# schematic_tsc.net
KiCad netlist of a schematic drawn in EAGLE
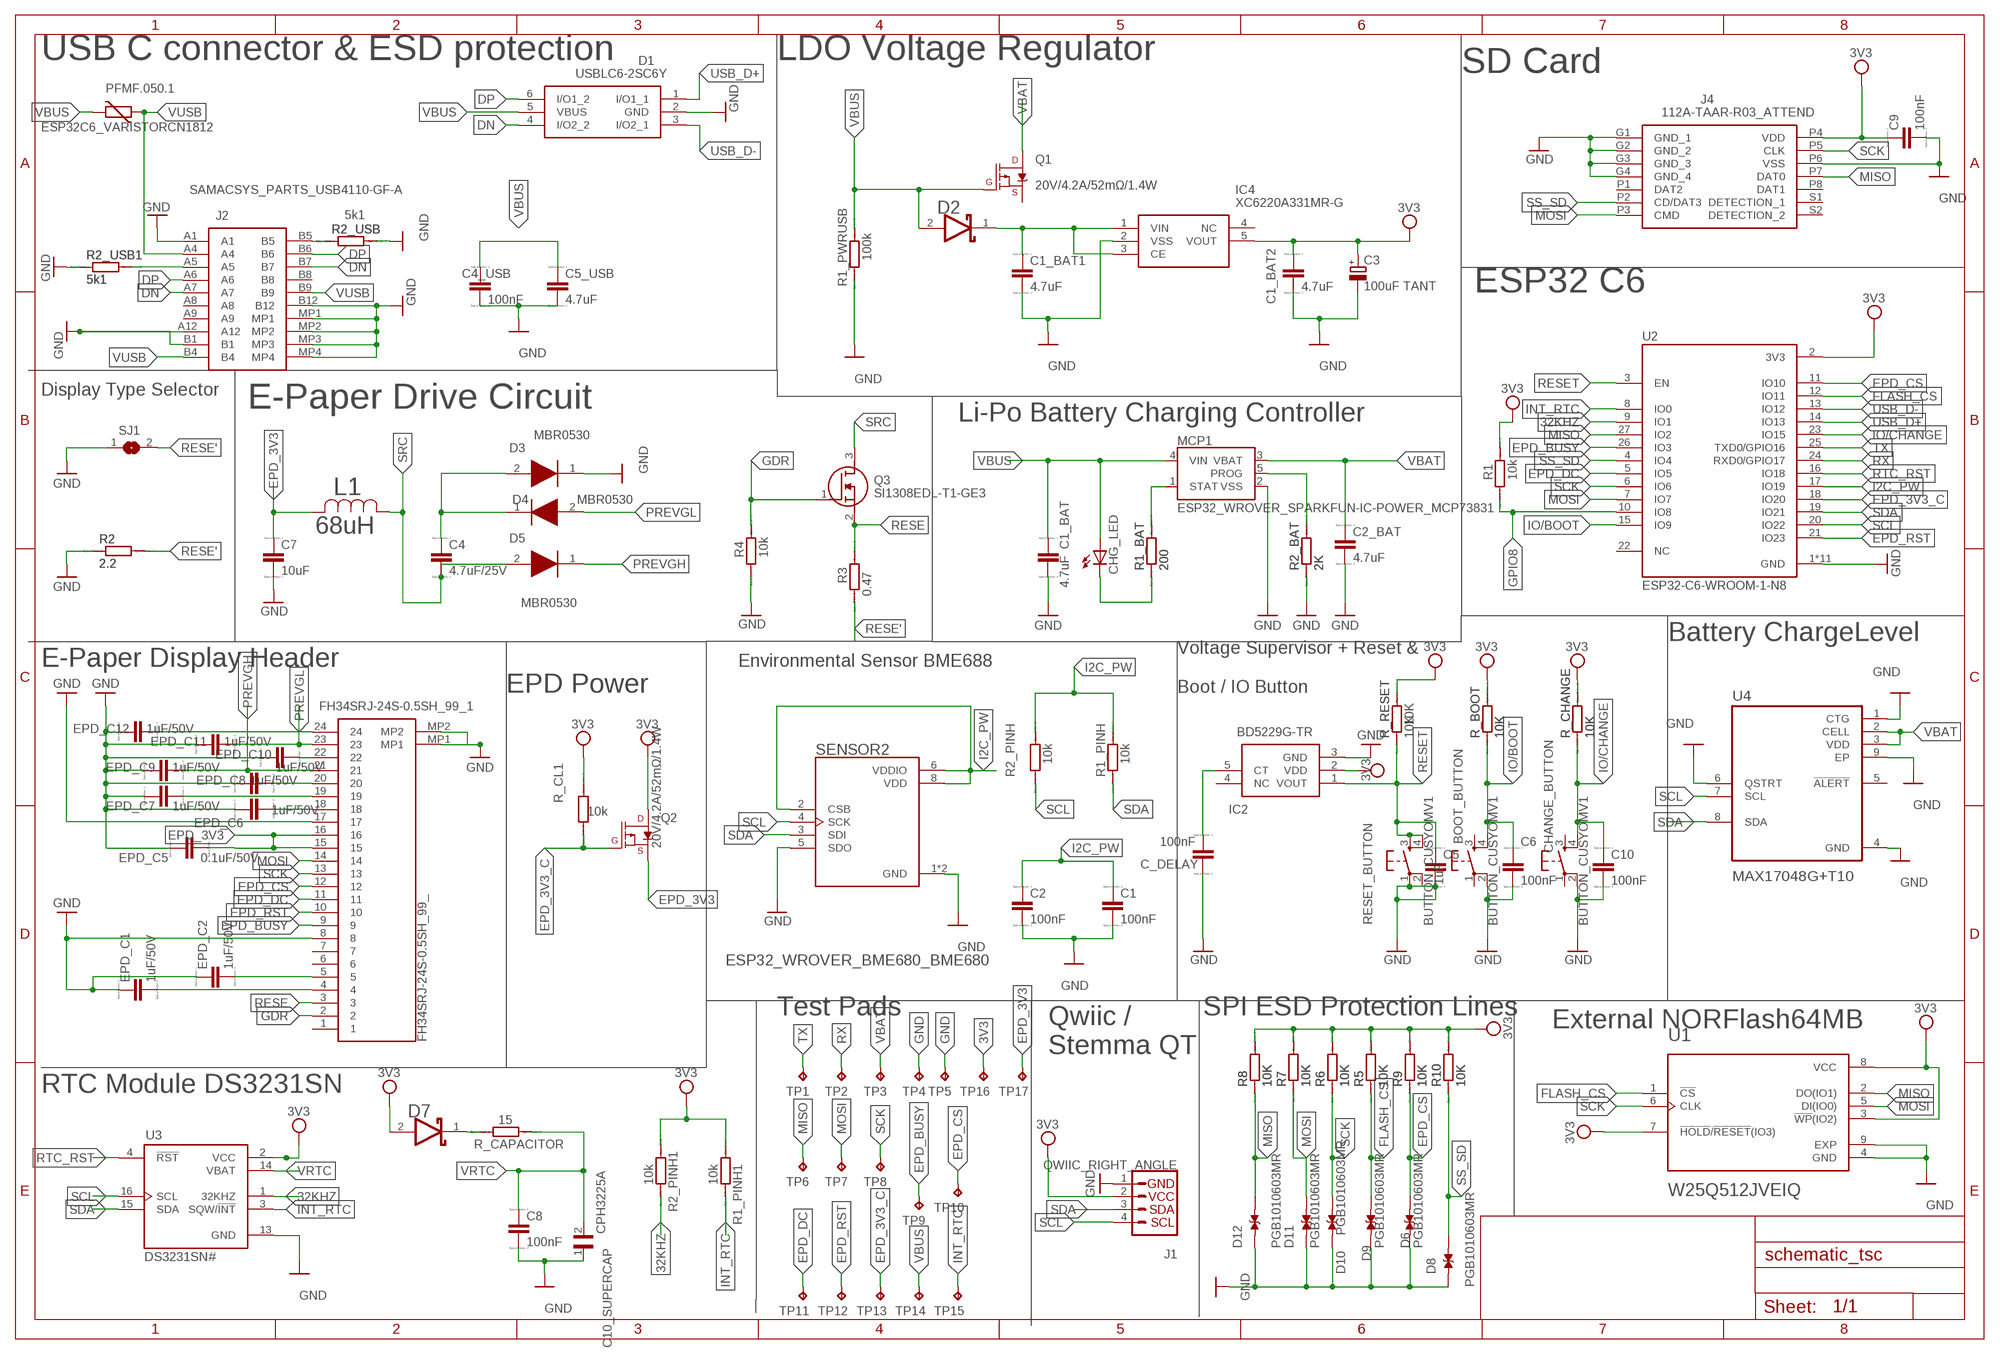
[diagram p0: schematic, sheet 1]

(export (version "E")
  (design (tool "Eeschema 10.0.6"))
  (components
    (comp (ref "BOOT_BUTTON")
      (value "BUTTON_CUSYOMV1")
      (footprint "eagle-import:MYBUTTON")
      (libsource (lib "eagle-import") (part "BUTTON_CUSYOMV1"))
    )
    (comp (ref "C1")
      (value "100nF")
      (footprint "eagle-import:EAGLE-LTSPICE_C0402")
      (libsource (lib "eagle-import") (part "EAGLE-LTSPICE_CC0402"))
    )
    (comp (ref "C1_BAT")
      (value "4.7uF")
      (footprint "eagle-import:EAGLE-LTSPICE_C0402")
      (libsource (lib "eagle-import") (part "EAGLE-LTSPICE_CC0402"))
    )
    (comp (ref "C1_BAT1")
      (value "4.7uF")
      (footprint "eagle-import:EAGLE-LTSPICE_C0402")
      (libsource (lib "eagle-import") (part "EAGLE-LTSPICE_CC0402"))
    )
    (comp (ref "C1_BAT2")
      (value "4.7uF")
      (footprint "eagle-import:EAGLE-LTSPICE_C0402")
      (libsource (lib "eagle-import") (part "EAGLE-LTSPICE_CC0402"))
    )
    (comp (ref "C2")
      (value "100nF")
      (footprint "eagle-import:EAGLE-LTSPICE_C0402")
      (libsource (lib "eagle-import") (part "EAGLE-LTSPICE_CC0402"))
    )
    (comp (ref "C2_BAT")
      (value "4.7uF")
      (footprint "eagle-import:EAGLE-LTSPICE_C0402")
      (libsource (lib "eagle-import") (part "EAGLE-LTSPICE_CC0402"))
    )
    (comp (ref "C3")
      (value "100uF TANT")
      (footprint "eagle-import:RCL_CT3528")
      (libsource (lib "eagle-import") (part "RCL_CPOL-EUCT3528"))
    )
    (comp (ref "C4")
      (value "4.7uF/25V")
      (footprint "eagle-import:EAGLE-LTSPICE_C0402")
      (libsource (lib "eagle-import") (part "EAGLE-LTSPICE_CC0402"))
    )
    (comp (ref "C4_USB")
      (value "100nF")
      (footprint "eagle-import:EAGLE-LTSPICE_C0402")
      (libsource (lib "eagle-import") (part "EAGLE-LTSPICE_CC0402"))
    )
    (comp (ref "C5")
      (value "1uF")
      (footprint "eagle-import:EAGLE-LTSPICE_C0402")
      (libsource (lib "eagle-import") (part "EAGLE-LTSPICE_CC0402"))
    )
    (comp (ref "C5_USB")
      (value "4.7uF")
      (footprint "eagle-import:EAGLE-LTSPICE_C0402")
      (libsource (lib "eagle-import") (part "EAGLE-LTSPICE_CC0402"))
    )
    (comp (ref "C6")
      (value "100nF")
      (footprint "eagle-import:EAGLE-LTSPICE_C0402")
      (libsource (lib "eagle-import") (part "EAGLE-LTSPICE_CC0402"))
    )
    (comp (ref "C7")
      (value "10uF")
      (footprint "eagle-import:EAGLE-LTSPICE_C0402")
      (libsource (lib "eagle-import") (part "EAGLE-LTSPICE_CC0402"))
    )
    (comp (ref "C8")
      (value "100nF")
      (footprint "eagle-import:EAGLE-LTSPICE_C0402")
      (libsource (lib "eagle-import") (part "EAGLE-LTSPICE_CC0402"))
    )
    (comp (ref "C9")
      (value "100nF")
      (footprint "eagle-import:EAGLE-LTSPICE_C0402")
      (libsource (lib "eagle-import") (part "EAGLE-LTSPICE_CC0402"))
    )
    (comp (ref "C10")
      (value "100nF")
      (footprint "eagle-import:EAGLE-LTSPICE_C0402")
      (libsource (lib "eagle-import") (part "EAGLE-LTSPICE_CC0402"))
    )
    (comp (ref "C10_SUPERCAP")
      (value "CPH3225A")
      (footprint "eagle-import:CAPCP3225X100N")
      (fields (field (name "MF") "Seiko Instruments"))
      (libsource (lib "eagle-import") (part "CPH3225A"))
    )
    (comp (ref "CHANGE_BUTTON")
      (value "BUTTON_CUSYOMV1")
      (footprint "eagle-import:MYBUTTON")
      (libsource (lib "eagle-import") (part "BUTTON_CUSYOMV1"))
    )
    (comp (ref "CHG_LED")
      (value "ADAFRUIT_LEDCHIP-LED0603")
      (footprint "eagle-import:ADAFRUIT_CHIP-LED0603")
      (libsource (lib "eagle-import") (part "ADAFRUIT_LEDCHIP-LED0603"))
    )
    (comp (ref "C_DELAY")
      (value "100nF")
      (footprint "eagle-import:EAGLE-LTSPICE_C0402")
      (libsource (lib "eagle-import") (part "EAGLE-LTSPICE_CC0402"))
    )
    (comp (ref "D1")
      (value "USBLC6-2SC6Y")
      (footprint "eagle-import:SOT95P280X145-6N")
      (fields (field (name "MF") "STMicroelectronics"))
      (libsource (lib "eagle-import") (part "USBLC6-2SC6Y"))
    )
    (comp (ref "D2")
      (value "ESP32_WROVER_AVX---SD0805S020S1R0_AVX_SD0805S020S1R0_0_0AVX_SD0805S020S1R0_0_0")
      (footprint "eagle-import:ESP32_WROVER_AVX---SD0805S020S1R0_AVX_SD0805S020S1R0_0")
      (fields
        (field (name "DIGIKEY_PART_NUMBER") "478-7800-1-ND")
        (field (name "MF") "AVX")
        (field (name "MOUSER_PART_NUMBER") "581-SD0805S020S1R0")
      )
      (libsource (lib "eagle-import") (part "ESP32_WROVER_AVX---SD0805S020S1R0_AVX_SD0805S020S1R0_0_0AVX_SD0805S020S1R0_0_0"))
    )
    (comp (ref "D3")
      (value "MBR0530")
      (footprint "eagle-import:SOD3716X135N")
      (fields (field (name "MF") "ON Semiconductor"))
      (libsource (lib "eagle-import") (part "MBR0530"))
    )
    (comp (ref "D4")
      (value "MBR0530")
      (footprint "eagle-import:SOD3716X135N")
      (fields (field (name "MF") "ON Semiconductor"))
      (libsource (lib "eagle-import") (part "MBR0530"))
    )
    (comp (ref "D5")
      (value "MBR0530")
      (footprint "eagle-import:SOD3716X135N")
      (fields (field (name "MF") "ON Semiconductor"))
      (libsource (lib "eagle-import") (part "MBR0530"))
    )
    (comp (ref "D6")
      (value "PGB1010603MR")
      (footprint "eagle-import:DIOC1608X36N")
      (fields (field (name "MF") "Littelfuse Inc."))
      (libsource (lib "eagle-import") (part "PGB1010603MR"))
    )
    (comp (ref "D7")
      (value "ESP32_WROVER_AVX---SD0805S020S1R0_AVX_SD0805S020S1R0_0_0AVX_SD0805S020S1R0_0_0")
      (footprint "eagle-import:ESP32_WROVER_AVX---SD0805S020S1R0_AVX_SD0805S020S1R0_0")
      (fields
        (field (name "DIGIKEY_PART_NUMBER") "478-7800-1-ND")
        (field (name "MF") "AVX")
        (field (name "MOUSER_PART_NUMBER") "581-SD0805S020S1R0")
      )
      (libsource (lib "eagle-import") (part "ESP32_WROVER_AVX---SD0805S020S1R0_AVX_SD0805S020S1R0_0_0AVX_SD0805S020S1R0_0_0"))
    )
    (comp (ref "D8")
      (value "PGB1010603MR")
      (footprint "eagle-import:DIOC1608X36N")
      (fields (field (name "MF") "Littelfuse Inc."))
      (libsource (lib "eagle-import") (part "PGB1010603MR"))
    )
    (comp (ref "D9")
      (value "PGB1010603MR")
      (footprint "eagle-import:DIOC1608X36N")
      (fields (field (name "MF") "Littelfuse Inc."))
      (libsource (lib "eagle-import") (part "PGB1010603MR"))
    )
    (comp (ref "D10")
      (value "PGB1010603MR")
      (footprint "eagle-import:DIOC1608X36N")
      (fields (field (name "MF") "Littelfuse Inc."))
      (libsource (lib "eagle-import") (part "PGB1010603MR"))
    )
    (comp (ref "D11")
      (value "PGB1010603MR")
      (footprint "eagle-import:DIOC1608X36N")
      (fields (field (name "MF") "Littelfuse Inc."))
      (libsource (lib "eagle-import") (part "PGB1010603MR"))
    )
    (comp (ref "D12")
      (value "PGB1010603MR")
      (footprint "eagle-import:DIOC1608X36N")
      (fields (field (name "MF") "Littelfuse Inc."))
      (libsource (lib "eagle-import") (part "PGB1010603MR"))
    )
    (comp (ref "EPD_C1")
      (value "1uF/50V")
      (footprint "eagle-import:EAGLE-LTSPICE_C0402")
      (libsource (lib "eagle-import") (part "EAGLE-LTSPICE_CC0402"))
    )
    (comp (ref "EPD_C2")
      (value "1uF/50V")
      (footprint "eagle-import:EAGLE-LTSPICE_C0402")
      (libsource (lib "eagle-import") (part "EAGLE-LTSPICE_CC0402"))
    )
    (comp (ref "EPD_C5")
      (value "0.1uF/50V")
      (footprint "eagle-import:EAGLE-LTSPICE_C0402")
      (libsource (lib "eagle-import") (part "EAGLE-LTSPICE_CC0402"))
    )
    (comp (ref "EPD_C6")
      (value "1uF/50V")
      (footprint "eagle-import:EAGLE-LTSPICE_C0402")
      (libsource (lib "eagle-import") (part "EAGLE-LTSPICE_CC0402"))
    )
    (comp (ref "EPD_C7")
      (value "1uF/50V")
      (footprint "eagle-import:EAGLE-LTSPICE_C0402")
      (libsource (lib "eagle-import") (part "EAGLE-LTSPICE_CC0402"))
    )
    (comp (ref "EPD_C8")
      (value "1uF/50V")
      (footprint "eagle-import:EAGLE-LTSPICE_C0402")
      (libsource (lib "eagle-import") (part "EAGLE-LTSPICE_CC0402"))
    )
    (comp (ref "EPD_C9")
      (value "1uF/50V")
      (footprint "eagle-import:EAGLE-LTSPICE_C0402")
      (libsource (lib "eagle-import") (part "EAGLE-LTSPICE_CC0402"))
    )
    (comp (ref "EPD_C10")
      (value "1uF/50V")
      (footprint "eagle-import:EAGLE-LTSPICE_C0402")
      (libsource (lib "eagle-import") (part "EAGLE-LTSPICE_CC0402"))
    )
    (comp (ref "EPD_C11")
      (value "1uF/50V")
      (footprint "eagle-import:EAGLE-LTSPICE_C0402")
      (libsource (lib "eagle-import") (part "EAGLE-LTSPICE_CC0402"))
    )
    (comp (ref "EPD_C12")
      (value "1uF/50V")
      (footprint "eagle-import:EAGLE-LTSPICE_C0402")
      (libsource (lib "eagle-import") (part "EAGLE-LTSPICE_CC0402"))
    )
    (comp (ref "FH34SRJ-24S-0.5SH_99_1")
      (value "FH34SRJ-24S-0.5SH_99_")
      (footprint "eagle-import:FH34SRJ24S05SH99")
      (fields
        (field (name "MANUFACTURER_PART_NUMBER") "FH34SRJ-24S-0.5SH(99)")
        (field (name "MOUSER_PART_NUMBER") "798-FH34SRJ24S05SH99")
      )
      (libsource (lib "eagle-import") (part "FH34SRJ-24S-0.5SH_99_"))
    )
    (comp (ref "IC2")
      (value "BD5229G-TR")
      (footprint "eagle-import:SOT95P280X125-5N")
      (fields (field (name "MOUSER_PART_NUMBER") "755-BD5229G-TR"))
      (libsource (lib "eagle-import") (part "BD5229G-TR"))
    )
    (comp (ref "IC4")
      (value "XC6220A331MR-G")
      (footprint "eagle-import:SOT95P280X120-5N")
      (fields (field (name "MOUSER_PART_NUMBER") "865-XC6220A331MR-G"))
      (libsource (lib "eagle-import") (part "XC6220A331MR-G"))
    )
    (comp (ref "J1")
      (value "QWIIC_RIGHT_ANGLE")
      (footprint "eagle-import:JST04_1MM_RA")
      (libsource (lib "eagle-import") (part "QWIIC_CONNECTORJS-1MM"))
    )
    (comp (ref "J2")
      (value "SAMACSYS_PARTS_USB4110-GF-A")
      (footprint "eagle-import:SAMACSYS_PARTS_USB4110GFA")
      (fields
        (field (name "MANUFACTURER_PART_NUMBER") "USB4110-GF-A")
        (field (name "MOUSER_PART_NUMBER") "640-USB4110-GF-A")
      )
      (libsource (lib "eagle-import") (part "SAMACSYS_PARTS_USB4110-GF-A"))
    )
    (comp (ref "J4")
      (value "112A-TAAR-R03_ATTEND")
      (footprint "eagle-import:112ATAARR03ATTEND")
      (fields (field (name "MANUFACTURER_PART_NUMBER") "112A-TAAR-R03 ATTEND"))
      (libsource (lib "eagle-import") (part "112A-TAAR-R03_ATTEND"))
    )
    (comp (ref "L1")
      (value "68uH")
      (footprint "eagle-import:IND_4828-WE-TPC_WRE")
      (fields
        (field (name "MANUFACTURER_PART_NUMBER") "744043680")
        (field (name "COPYRIGHT") "Copyright (C) 2024 Ultra Librarian. All rights reserved.")
      )
      (libsource (lib "eagle-import") (part "744043680IND_4828-WE-TPC_WRE"))
    )
    (comp (ref "MCP1")
      (value "ESP32_WROVER_SPARKFUN-IC-POWER_MCP73831")
      (footprint "eagle-import:ESP32_WROVER_SPARKFUN-IC-POWER_SOT23-5")
      (libsource (lib "eagle-import") (part "ESP32_WROVER_SPARKFUN-IC-POWER_MCP73831"))
    )
    (comp (ref "PFMF.050.1")
      (value "ESP32C6_VARISTORCN1812")
      (footprint "eagle-import:ESP32C6_VARISTOR_CT_CN1812")
      (libsource (lib "eagle-import") (part "ESP32C6_VARISTORCN1812"))
    )
    (comp (ref "Q1")
      (value "20V/4.2A/52mΩ/1.4W")
      (footprint "eagle-import:ESP32_WROVER_SPARKFUN-DISCRETESEMI_SOT23-3")
      (libsource (lib "eagle-import") (part "ESP32_WROVER_SPARKFUN-DISCRETESEMI_MOSFET_PCH-DMG2305UX-7"))
    )
    (comp (ref "Q2")
      (value "20V/4.2A/52mΩ/1.4W")
      (footprint "eagle-import:ESP32_WROVER_SPARKFUN-DISCRETESEMI_SOT23-3")
      (libsource (lib "eagle-import") (part "ESP32_WROVER_SPARKFUN-DISCRETESEMI_MOSFET_PCH-DMG2305UX-7"))
    )
    (comp (ref "Q3")
      (value "SI1308EDL-T1-GE3")
      (footprint "eagle-import:SOT65P210X110-3N")
      (fields (field (name "MF") "Vishay Siliconix"))
      (libsource (lib "eagle-import") (part "SI1308EDL-T1-GE3"))
    )
    (comp (ref "R1")
      (value "10k")
      (footprint "eagle-import:ESP32_WROVER_EAGLE-LTSPICE_R0402")
      (libsource (lib "eagle-import") (part "ESP32_WROVER_EAGLE-LTSPICE_RR0402"))
    )
    (comp (ref "R1_BAT")
      (value "200")
      (footprint "eagle-import:ESP32_WROVER_EAGLE-LTSPICE_R0402")
      (libsource (lib "eagle-import") (part "ESP32_WROVER_EAGLE-LTSPICE_RR0402"))
    )
    (comp (ref "R1_PINH")
      (value "10k")
      (footprint "eagle-import:ESP32_WROVER_EAGLE-LTSPICE_R0402")
      (libsource (lib "eagle-import") (part "ESP32_WROVER_EAGLE-LTSPICE_RR0402"))
    )
    (comp (ref "R1_PINH1")
      (value "10k")
      (footprint "eagle-import:ESP32_WROVER_EAGLE-LTSPICE_R0402")
      (libsource (lib "eagle-import") (part "ESP32_WROVER_EAGLE-LTSPICE_RR0402"))
    )
    (comp (ref "R1_PWRUSB")
      (value "100k")
      (footprint "eagle-import:ESP32_WROVER_EAGLE-LTSPICE_R0402")
      (libsource (lib "eagle-import") (part "ESP32_WROVER_EAGLE-LTSPICE_RR0402"))
    )
    (comp (ref "R2")
      (value "2.2")
      (footprint "eagle-import:ESP32_WROVER_EAGLE-LTSPICE_R0402")
      (libsource (lib "eagle-import") (part "ESP32_WROVER_EAGLE-LTSPICE_RR0402"))
    )
    (comp (ref "R2_BAT")
      (value "2K")
      (footprint "eagle-import:ESP32_WROVER_EAGLE-LTSPICE_R0402")
      (libsource (lib "eagle-import") (part "ESP32_WROVER_EAGLE-LTSPICE_RR0402"))
    )
    (comp (ref "R2_PINH")
      (value "10k")
      (footprint "eagle-import:ESP32_WROVER_EAGLE-LTSPICE_R0402")
      (libsource (lib "eagle-import") (part "ESP32_WROVER_EAGLE-LTSPICE_RR0402"))
    )
    (comp (ref "R2_PINH1")
      (value "10k")
      (footprint "eagle-import:ESP32_WROVER_EAGLE-LTSPICE_R0402")
      (libsource (lib "eagle-import") (part "ESP32_WROVER_EAGLE-LTSPICE_RR0402"))
    )
    (comp (ref "R2_USB")
      (value "5k1")
      (footprint "eagle-import:ESP32_WROVER_EAGLE-LTSPICE_R0402")
      (libsource (lib "eagle-import") (part "ESP32_WROVER_EAGLE-LTSPICE_RR0402"))
    )
    (comp (ref "R2_USB1")
      (value "5k1")
      (footprint "eagle-import:ESP32_WROVER_EAGLE-LTSPICE_R0402")
      (libsource (lib "eagle-import") (part "ESP32_WROVER_EAGLE-LTSPICE_RR0402"))
    )
    (comp (ref "R3")
      (value "0.47")
      (footprint "eagle-import:ESP32_WROVER_EAGLE-LTSPICE_R0402")
      (libsource (lib "eagle-import") (part "ESP32_WROVER_EAGLE-LTSPICE_RR0402"))
    )
    (comp (ref "R4")
      (value "10k")
      (footprint "eagle-import:ESP32_WROVER_EAGLE-LTSPICE_R0402")
      (libsource (lib "eagle-import") (part "ESP32_WROVER_EAGLE-LTSPICE_RR0402"))
    )
    (comp (ref "R5")
      (value "10K")
      (footprint "eagle-import:ESP32_WROVER_EAGLE-LTSPICE_R0402")
      (libsource (lib "eagle-import") (part "ESP32_WROVER_EAGLE-LTSPICE_RR0402"))
    )
    (comp (ref "R6")
      (value "10K")
      (footprint "eagle-import:ESP32_WROVER_EAGLE-LTSPICE_R0402")
      (libsource (lib "eagle-import") (part "ESP32_WROVER_EAGLE-LTSPICE_RR0402"))
    )
    (comp (ref "R7")
      (value "10K")
      (footprint "eagle-import:ESP32_WROVER_EAGLE-LTSPICE_R0402")
      (libsource (lib "eagle-import") (part "ESP32_WROVER_EAGLE-LTSPICE_RR0402"))
    )
    (comp (ref "R8")
      (value "10K")
      (footprint "eagle-import:ESP32_WROVER_EAGLE-LTSPICE_R0402")
      (libsource (lib "eagle-import") (part "ESP32_WROVER_EAGLE-LTSPICE_RR0402"))
    )
    (comp (ref "R9")
      (value "10K")
      (footprint "eagle-import:ESP32_WROVER_EAGLE-LTSPICE_R0402")
      (libsource (lib "eagle-import") (part "ESP32_WROVER_EAGLE-LTSPICE_RR0402"))
    )
    (comp (ref "R10")
      (value "10K")
      (footprint "eagle-import:ESP32_WROVER_EAGLE-LTSPICE_R0402")
      (libsource (lib "eagle-import") (part "ESP32_WROVER_EAGLE-LTSPICE_RR0402"))
    )
    (comp (ref "RESET_BUTTON")
      (value "BUTTON_CUSYOMV1")
      (footprint "eagle-import:MYBUTTON")
      (libsource (lib "eagle-import") (part "BUTTON_CUSYOMV1"))
    )
    (comp (ref "R_BOOT")
      (value "10K")
      (footprint "eagle-import:ESP32_WROVER_EAGLE-LTSPICE_R0402")
      (libsource (lib "eagle-import") (part "ESP32_WROVER_EAGLE-LTSPICE_RR0402"))
    )
    (comp (ref "R_CAPACITOR")
      (value "15")
      (footprint "eagle-import:ESP32_WROVER_EAGLE-LTSPICE_R0402")
      (libsource (lib "eagle-import") (part "ESP32_WROVER_EAGLE-LTSPICE_RR0402"))
    )
    (comp (ref "R_CHANGE")
      (value "10K")
      (footprint "eagle-import:ESP32_WROVER_EAGLE-LTSPICE_R0402")
      (libsource (lib "eagle-import") (part "ESP32_WROVER_EAGLE-LTSPICE_RR0402"))
    )
    (comp (ref "R_CL1")
      (value "10k")
      (footprint "eagle-import:ESP32_WROVER_EAGLE-LTSPICE_R0402")
      (libsource (lib "eagle-import") (part "ESP32_WROVER_EAGLE-LTSPICE_RR0402"))
    )
    (comp (ref "R_RESET")
      (value "10K")
      (footprint "eagle-import:ESP32_WROVER_EAGLE-LTSPICE_R0402")
      (libsource (lib "eagle-import") (part "ESP32_WROVER_EAGLE-LTSPICE_RR0402"))
    )
    (comp (ref "SENSOR2")
      (value "ESP32_WROVER_BME680_BME680")
      (footprint "eagle-import:ESP32_WROVER_BME680_PSON80P300X300X100-8N")
      (fields (field (name "MF") "Bosch Sensortec") (field (name "MP") "BME680"))
      (libsource (lib "eagle-import") (part "ESP32_WROVER_BME680_BME680"))
    )
    (comp (ref "SJ1") (value "SJ") (footprint "eagle-import:SJ") (libsource (lib "eagle-import") (part "SJ")))
    (comp (ref "TP1")
      (value "TPTP20R")
      (footprint "eagle-import:TP20R")
      (libsource (lib "eagle-import") (part "TPTP20R"))
    )
    (comp (ref "TP2")
      (value "TPTP20R")
      (footprint "eagle-import:TP20R")
      (libsource (lib "eagle-import") (part "TPTP20R"))
    )
    (comp (ref "TP3")
      (value "TPTP20R")
      (footprint "eagle-import:TP20R")
      (libsource (lib "eagle-import") (part "TPTP20R"))
    )
    (comp (ref "TP4")
      (value "TPTP20R")
      (footprint "eagle-import:TP20R")
      (libsource (lib "eagle-import") (part "TPTP20R"))
    )
    (comp (ref "TP5")
      (value "TPTP20R")
      (footprint "eagle-import:TP20R")
      (libsource (lib "eagle-import") (part "TPTP20R"))
    )
    (comp (ref "TP6")
      (value "TPTP20R")
      (footprint "eagle-import:TP20R")
      (libsource (lib "eagle-import") (part "TPTP20R"))
    )
    (comp (ref "TP7")
      (value "TPTP20R")
      (footprint "eagle-import:TP20R")
      (libsource (lib "eagle-import") (part "TPTP20R"))
    )
    (comp (ref "TP8")
      (value "TPTP20R")
      (footprint "eagle-import:TP20R")
      (libsource (lib "eagle-import") (part "TPTP20R"))
    )
    (comp (ref "TP9")
      (value "TPTP20R")
      (footprint "eagle-import:TP20R")
      (libsource (lib "eagle-import") (part "TPTP20R"))
    )
    (comp (ref "TP10")
      (value "TPTP20R")
      (footprint "eagle-import:TP20R")
      (libsource (lib "eagle-import") (part "TPTP20R"))
    )
    (comp (ref "TP11")
      (value "TPTP20R")
      (footprint "eagle-import:TP20R")
      (libsource (lib "eagle-import") (part "TPTP20R"))
    )
    (comp (ref "TP12")
      (value "TPTP20R")
      (footprint "eagle-import:TP20R")
      (libsource (lib "eagle-import") (part "TPTP20R"))
    )
    (comp (ref "TP13")
      (value "TPTP20R")
      (footprint "eagle-import:TP20R")
      (libsource (lib "eagle-import") (part "TPTP20R"))
    )
    (comp (ref "TP14")
      (value "TPTP20R")
      (footprint "eagle-import:TP20R")
      (libsource (lib "eagle-import") (part "TPTP20R"))
    )
    (comp (ref "TP15")
      (value "TPTP20R")
      (footprint "eagle-import:TP20R")
      (libsource (lib "eagle-import") (part "TPTP20R"))
    )
    (comp (ref "TP16")
      (value "TPTP20R")
      (footprint "eagle-import:TP20R")
      (libsource (lib "eagle-import") (part "TPTP20R"))
    )
    (comp (ref "TP17")
      (value "TPTP20R")
      (footprint "eagle-import:TP20R")
      (libsource (lib "eagle-import") (part "TPTP20R"))
    )
    (comp (ref "U1")
      (value "W25Q512JVEIQ")
      (footprint "eagle-import:SON127P600X800X80-9N")
      (fields (field (name "MF") "Winbond Electronics"))
      (libsource (lib "eagle-import") (part "W25Q512JVEIQ"))
    )
    (comp (ref "U2")
      (value "ESP32-C6-WROOM-1-N8")
      (footprint "eagle-import:XCVR_ESP32-C6-WROOM-1-N8")
      (fields (field (name "MF") "Espressif Systems"))
      (libsource (lib "eagle-import") (part "ESP32-C6-WROOM-1-N8"))
    )
    (comp (ref "U3")
      (value "DS3231SN#")
      (footprint "eagle-import:SOIC127P1032X265-16N")
      (fields (field (name "MF") "Analog Devices"))
      (libsource (lib "eagle-import") (part "DS3231SN#"))
    )
    (comp (ref "U4")
      (value "MAX17048G+T10")
      (footprint "eagle-import:SON50P200X200X80-9N")
      (fields (field (name "MF") "Analog Devices"))
      (libsource (lib "eagle-import") (part "MAX17048G+T10"))
    )
  )
  (nets
    (net (code "1") (name "3V3") (class "Default")
      (node (ref "C1_BAT2") (pin "1") (pinfunction "1_1") (pintype "passive"))
      (node (ref "C3") (pin "+") (pinfunction "+_+") (pintype "passive"))
      (node (ref "C9") (pin "1") (pinfunction "1_1") (pintype "passive"))
      (node (ref "D7") (pin "2") (pinfunction "ANODE_2") (pintype "bidirectional"))
      (node (ref "IC2") (pin "2") (pinfunction "VDD_2") (pintype "bidirectional"))
      (node (ref "IC4") (pin "5") (pinfunction "VOUT_5") (pintype "bidirectional"))
      (node (ref "J1") (pin "2") (pinfunction "2_2") (pintype "power_in"))
      (node (ref "J4") (pin "P4") (pinfunction "VDD_P4") (pintype "bidirectional"))
      (node (ref "Q2") (pin "3") (pinfunction "D_3") (pintype "bidirectional"))
      (node (ref "R1") (pin "2") (pinfunction "2_2") (pintype "passive"))
      (node (ref "R10") (pin "2") (pinfunction "2_2") (pintype "passive"))
      (node (ref "R1_PINH1") (pin "1") (pinfunction "1_1") (pintype "passive"))
      (node (ref "R2_PINH1") (pin "1") (pinfunction "1_1") (pintype "passive"))
      (node (ref "R5") (pin "2") (pinfunction "2_2") (pintype "passive"))
      (node (ref "R6") (pin "2") (pinfunction "2_2") (pintype "passive"))
      (node (ref "R7") (pin "2") (pinfunction "2_2") (pintype "passive"))
      (node (ref "R8") (pin "2") (pinfunction "2_2") (pintype "passive"))
      (node (ref "R9") (pin "2") (pinfunction "2_2") (pintype "passive"))
      (node (ref "R_BOOT") (pin "2") (pinfunction "2_2") (pintype "passive"))
      (node (ref "R_CHANGE") (pin "2") (pinfunction "2_2") (pintype "passive"))
      (node (ref "R_CL1") (pin "2") (pinfunction "2_2") (pintype "passive"))
      (node (ref "R_RESET") (pin "2") (pinfunction "2_2") (pintype "passive"))
      (node (ref "TP16") (pin "TP") (pinfunction "TP_TP") (pintype "input"))
      (node (ref "U1") (pin "3") (pinfunction "~{WP}(IO2)_3") (pintype "bidirectional"))
      (node (ref "U1") (pin "7") (pinfunction "~{HOLD}/~{RESET}(IO3)_7") (pintype "bidirectional"))
      (node (ref "U1") (pin "8") (pinfunction "VCC_8") (pintype "power_in"))
      (node (ref "U2") (pin "2") (pinfunction "3V3_2") (pintype "power_in"))
      (node (ref "U3") (pin "2") (pinfunction "VCC_2") (pintype "power_in"))
    )
    (net (code "2") (name "32KHZ") (class "Default")
      (node (ref "R2_PINH1") (pin "2") (pinfunction "2_2") (pintype "passive"))
      (node (ref "U2") (pin "9") (pinfunction "IO1_9") (pintype "bidirectional"))
      (node (ref "U3") (pin "1") (pinfunction "32KHZ_1") (pintype "output"))
    )
    (net (code "3") (name "DN") (class "Default")
      (node (ref "D1") (pin "4") (pinfunction "I/O2_2_4") (pintype "bidirectional"))
      (node (ref "J2") (pin "A7") (pinfunction "A7_A7") (pintype "bidirectional"))
      (node (ref "J2") (pin "B7") (pinfunction "B7_B7") (pintype "bidirectional"))
    )
    (net (code "4") (name "DP") (class "Default")
      (node (ref "D1") (pin "6") (pinfunction "I/O1_2_6") (pintype "bidirectional"))
      (node (ref "J2") (pin "A6") (pinfunction "A6_A6") (pintype "bidirectional"))
      (node (ref "J2") (pin "B6") (pinfunction "B6_B6") (pintype "bidirectional"))
    )
    (net (code "5") (name "EPD_3V3") (class "Default")
      (node (ref "C7") (pin "1") (pinfunction "1_1") (pintype "passive"))
      (node (ref "EPD_C5") (pin "2") (pinfunction "2_2") (pintype "passive"))
      (node (ref "FH34SRJ-24S-0.5SH_99_1") (pin "15") (pinfunction "15_15") (pintype "bidirectional"))
      (node (ref "FH34SRJ-24S-0.5SH_99_1") (pin "16") (pinfunction "16_16") (pintype "bidirectional"))
      (node (ref "L1") (pin "2") (pinfunction "2_2") (pintype "passive"))
      (node (ref "Q2") (pin "2") (pinfunction "S_2") (pintype "bidirectional"))
      (node (ref "TP17") (pin "TP") (pinfunction "TP_TP") (pintype "input"))
    )
    (net (code "6") (name "EPD_3V3_C") (class "Default")
      (node (ref "Q2") (pin "1") (pinfunction "G_1") (pintype "bidirectional"))
      (node (ref "R_CL1") (pin "1") (pinfunction "1_1") (pintype "passive"))
      (node (ref "TP13") (pin "TP") (pinfunction "TP_TP") (pintype "input"))
      (node (ref "U2") (pin "18") (pinfunction "IO20_18") (pintype "bidirectional"))
    )
    (net (code "7") (name "EPD_BUSY") (class "Default")
      (node (ref "FH34SRJ-24S-0.5SH_99_1") (pin "9") (pinfunction "9_9") (pintype "bidirectional"))
      (node (ref "TP9") (pin "TP") (pinfunction "TP_TP") (pintype "input"))
      (node (ref "U2") (pin "26") (pinfunction "IO3_26") (pintype "bidirectional"))
    )
    (net (code "8") (name "EPD_CS") (class "Default")
      (node (ref "D6") (pin "2") (pinfunction "2_2") (pintype "passive"))
      (node (ref "FH34SRJ-24S-0.5SH_99_1") (pin "12") (pinfunction "12_12") (pintype "bidirectional"))
      (node (ref "R9") (pin "1") (pinfunction "1_1") (pintype "passive"))
      (node (ref "TP10") (pin "TP") (pinfunction "TP_TP") (pintype "input"))
      (node (ref "U2") (pin "11") (pinfunction "IO10_11") (pintype "bidirectional"))
    )
    (net (code "9") (name "EPD_DC") (class "Default")
      (node (ref "FH34SRJ-24S-0.5SH_99_1") (pin "11") (pinfunction "11_11") (pintype "bidirectional"))
      (node (ref "TP11") (pin "TP") (pinfunction "TP_TP") (pintype "input"))
      (node (ref "U2") (pin "5") (pinfunction "IO5_5") (pintype "bidirectional"))
    )
    (net (code "10") (name "EPD_RST") (class "Default")
      (node (ref "FH34SRJ-24S-0.5SH_99_1") (pin "10") (pinfunction "10_10") (pintype "bidirectional"))
      (node (ref "TP12") (pin "TP") (pinfunction "TP_TP") (pintype "input"))
      (node (ref "U2") (pin "21") (pinfunction "IO23_21") (pintype "bidirectional"))
    )
    (net (code "11") (name "FLASH_CS") (class "Default")
      (node (ref "D9") (pin "2") (pinfunction "2_2") (pintype "passive"))
      (node (ref "R5") (pin "1") (pinfunction "1_1") (pintype "passive"))
      (node (ref "U1") (pin "1") (pinfunction "~{CS}_1") (pintype "input"))
      (node (ref "U2") (pin "12") (pinfunction "IO11_12") (pintype "bidirectional"))
    )
    (net (code "12") (name "GDR") (class "Default")
      (node (ref "FH34SRJ-24S-0.5SH_99_1") (pin "2") (pinfunction "2_2") (pintype "bidirectional"))
      (node (ref "Q3") (pin "1") (pinfunction "G_1") (pintype "bidirectional"))
      (node (ref "R4") (pin "2") (pinfunction "2_2") (pintype "passive"))
    )
    (net (code "13") (name "GND") (class "Default")
      (node (ref "BOOT_BUTTON") (pin "2") (pinfunction "2_2") (pintype "passive"))
      (node (ref "C1") (pin "2") (pinfunction "2_2") (pintype "passive"))
      (node (ref "C10") (pin "2") (pinfunction "2_2") (pintype "passive"))
      (node (ref "C10_SUPERCAP") (pin "1") (pinfunction "1_1") (pintype "passive"))
      (node (ref "C1_BAT") (pin "2") (pinfunction "2_2") (pintype "passive"))
      (node (ref "C1_BAT1") (pin "2") (pinfunction "2_2") (pintype "passive"))
      (node (ref "C1_BAT2") (pin "2") (pinfunction "2_2") (pintype "passive"))
      (node (ref "C2") (pin "2") (pinfunction "2_2") (pintype "passive"))
      (node (ref "C2_BAT") (pin "2") (pinfunction "2_2") (pintype "passive"))
      (node (ref "C3") (pin "-") (pinfunction "-_-") (pintype "passive"))
      (node (ref "C4_USB") (pin "2") (pinfunction "2_2") (pintype "passive"))
      (node (ref "C5") (pin "2") (pinfunction "2_2") (pintype "passive"))
      (node (ref "C5_USB") (pin "2") (pinfunction "2_2") (pintype "passive"))
      (node (ref "C6") (pin "2") (pinfunction "2_2") (pintype "passive"))
      (node (ref "C7") (pin "2") (pinfunction "2_2") (pintype "passive"))
      (node (ref "C8") (pin "2") (pinfunction "2_2") (pintype "passive"))
      (node (ref "C9") (pin "2") (pinfunction "2_2") (pintype "passive"))
      (node (ref "CHANGE_BUTTON") (pin "2") (pinfunction "2_2") (pintype "passive"))
      (node (ref "C_DELAY") (pin "1") (pinfunction "1_1") (pintype "passive"))
      (node (ref "D1") (pin "2") (pinfunction "GND_2") (pintype "bidirectional"))
      (node (ref "D10") (pin "1") (pinfunction "1_1") (pintype "passive"))
      (node (ref "D11") (pin "1") (pinfunction "1_1") (pintype "passive"))
      (node (ref "D12") (pin "1") (pinfunction "1_1") (pintype "passive"))
      (node (ref "D3") (pin "1") (pinfunction "K_1") (pintype "bidirectional"))
      (node (ref "D6") (pin "1") (pinfunction "1_1") (pintype "passive"))
      (node (ref "D8") (pin "1") (pinfunction "1_1") (pintype "passive"))
      (node (ref "D9") (pin "1") (pinfunction "1_1") (pintype "passive"))
      (node (ref "EPD_C1") (pin "1") (pinfunction "1_1") (pintype "passive"))
      (node (ref "EPD_C10") (pin "1") (pinfunction "1_1") (pintype "passive"))
      (node (ref "EPD_C11") (pin "1") (pinfunction "1_1") (pintype "passive"))
      (node (ref "EPD_C12") (pin "1") (pinfunction "1_1") (pintype "passive"))
      (node (ref "EPD_C2") (pin "1") (pinfunction "1_1") (pintype "passive"))
      (node (ref "EPD_C5") (pin "1") (pinfunction "1_1") (pintype "passive"))
      (node (ref "EPD_C6") (pin "1") (pinfunction "1_1") (pintype "passive"))
      (node (ref "EPD_C7") (pin "1") (pinfunction "1_1") (pintype "passive"))
      (node (ref "EPD_C8") (pin "1") (pinfunction "1_1") (pintype "passive"))
      (node (ref "EPD_C9") (pin "1") (pinfunction "1_1") (pintype "passive"))
      (node (ref "FH34SRJ-24S-0.5SH_99_1") (pin "17") (pinfunction "17_17") (pintype "bidirectional"))
      (node (ref "FH34SRJ-24S-0.5SH_99_1") (pin "8") (pinfunction "8_8") (pintype "bidirectional"))
      (node (ref "FH34SRJ-24S-0.5SH_99_1") (pin "MP1") (pinfunction "MP1_MP1") (pintype "bidirectional"))
      (node (ref "FH34SRJ-24S-0.5SH_99_1") (pin "MP2") (pinfunction "MP2_MP2") (pintype "bidirectional"))
      (node (ref "IC2") (pin "3") (pinfunction "GND_3") (pintype "bidirectional"))
      (node (ref "IC4") (pin "2") (pinfunction "VSS_2") (pintype "bidirectional"))
      (node (ref "J1") (pin "1") (pinfunction "1_1") (pintype "power_in"))
      (node (ref "J2") (pin "A1") (pinfunction "A1_A1") (pintype "bidirectional"))
      (node (ref "J2") (pin "A12") (pinfunction "A12_A12") (pintype "bidirectional"))
      (node (ref "J2") (pin "B1") (pinfunction "B1_B1") (pintype "bidirectional"))
      (node (ref "J2") (pin "B12") (pinfunction "B12_B12") (pintype "bidirectional"))
      (node (ref "J2") (pin "MP1") (pinfunction "MP1_MP1") (pintype "bidirectional"))
      (node (ref "J2") (pin "MP2") (pinfunction "MP2_MP2") (pintype "bidirectional"))
      (node (ref "J2") (pin "MP3") (pinfunction "MP3_MP3") (pintype "bidirectional"))
      (node (ref "J2") (pin "MP4") (pinfunction "MP4_MP4") (pintype "bidirectional"))
      (node (ref "J4") (pin "G1") (pinfunction "GND_1_G1") (pintype "bidirectional"))
      (node (ref "J4") (pin "G2") (pinfunction "GND_2_G2") (pintype "bidirectional"))
      (node (ref "J4") (pin "G3") (pinfunction "GND_3_G3") (pintype "bidirectional"))
      (node (ref "J4") (pin "G4") (pinfunction "GND_4_G4") (pintype "bidirectional"))
      (node (ref "J4") (pin "P6") (pinfunction "VSS_P6") (pintype "bidirectional"))
      (node (ref "MCP1") (pin "2") (pinfunction "VSS_2") (pintype "power_in"))
      (node (ref "R1_PWRUSB") (pin "1") (pinfunction "1_1") (pintype "passive"))
      (node (ref "R2") (pin "1") (pinfunction "1_1") (pintype "passive"))
      (node (ref "R2_BAT") (pin "1") (pinfunction "1_1") (pintype "passive"))
      (node (ref "R2_USB") (pin "2") (pinfunction "2_2") (pintype "passive"))
      (node (ref "R2_USB1") (pin "1") (pinfunction "1_1") (pintype "passive"))
      (node (ref "R4") (pin "1") (pinfunction "1_1") (pintype "passive"))
      (node (ref "RESET_BUTTON") (pin "1") (pinfunction "1_1") (pintype "passive"))
      (node (ref "RESET_BUTTON") (pin "2") (pinfunction "2_2") (pintype "passive"))
      (node (ref "SENSOR2") (pin "1") (pinfunction "GND_1") (pintype "power_in"))
      (node (ref "SENSOR2") (pin "5") (pinfunction "SDO_5") (pintype "bidirectional"))
      (node (ref "SENSOR2") (pin "7") (pinfunction "GND_7") (pintype "power_in"))
      (node (ref "SJ1") (pin "1") (pinfunction "1_1") (pintype "passive"))
      (node (ref "TP4") (pin "TP") (pinfunction "TP_TP") (pintype "input"))
      (node (ref "TP5") (pin "TP") (pinfunction "TP_TP") (pintype "input"))
      (node (ref "U1") (pin "4") (pinfunction "GND_4") (pintype "power_in"))
      (node (ref "U1") (pin "9") (pinfunction "EXP_9") (pintype "passive"))
      (node (ref "U2") (pin "1") (pinfunction "GND_1") (pintype "power_in"))
      (node (ref "U2") (pin "28") (pinfunction "GND_28") (pintype "power_in"))
      (node (ref "U2") (pin "29_1") (pinfunction "GND_29_1") (pintype "power_in"))
      (node (ref "U2") (pin "29_2") (pinfunction "GND_29_2") (pintype "power_in"))
      (node (ref "U2") (pin "29_3") (pinfunction "GND_29_3") (pintype "power_in"))
      (node (ref "U2") (pin "29_4") (pinfunction "GND_29_4") (pintype "power_in"))
      (node (ref "U2") (pin "29_5") (pinfunction "GND_29_5") (pintype "power_in"))
      (node (ref "U2") (pin "29_6") (pinfunction "GND_29_6") (pintype "power_in"))
      (node (ref "U2") (pin "29_7") (pinfunction "GND_29_7") (pintype "power_in"))
      (node (ref "U2") (pin "29_8") (pinfunction "GND_29_8") (pintype "power_in"))
      (node (ref "U2") (pin "29_9") (pinfunction "GND_29_9") (pintype "power_in"))
      (node (ref "U3") (pin "13") (pinfunction "GND_13") (pintype "power_in"))
      (node (ref "U4") (pin "1") (pinfunction "CTG_1") (pintype "power_in"))
      (node (ref "U4") (pin "4") (pinfunction "GND_4") (pintype "power_in"))
      (node (ref "U4") (pin "6") (pinfunction "QSTRT_6") (pintype "input"))
      (node (ref "U4") (pin "9") (pinfunction "EP_9") (pintype "power_in"))
    )
    (net (code "14") (name "GPIO8") (class "Default")
      (node (ref "R1") (pin "1") (pinfunction "1_1") (pintype "passive"))
      (node (ref "U2") (pin "10") (pinfunction "IO8_10") (pintype "bidirectional"))
    )
    (net (code "15") (name "I2C_PW") (class "Default")
      (node (ref "C1") (pin "1") (pinfunction "1_1") (pintype "passive"))
      (node (ref "C2") (pin "1") (pinfunction "1_1") (pintype "passive"))
      (node (ref "R1_PINH") (pin "2") (pinfunction "2_2") (pintype "passive"))
      (node (ref "R2_PINH") (pin "2") (pinfunction "2_2") (pintype "passive"))
      (node (ref "SENSOR2") (pin "2") (pinfunction "CSB_2") (pintype "input"))
      (node (ref "SENSOR2") (pin "6") (pinfunction "VDDIO_6") (pintype "power_in"))
      (node (ref "SENSOR2") (pin "8") (pinfunction "VDD_8") (pintype "power_in"))
      (node (ref "U2") (pin "17") (pinfunction "IO19_17") (pintype "bidirectional"))
    )
    (net (code "16") (name "INT_RTC") (class "Default")
      (node (ref "R1_PINH1") (pin "2") (pinfunction "2_2") (pintype "passive"))
      (node (ref "TP15") (pin "TP") (pinfunction "TP_TP") (pintype "input"))
      (node (ref "U2") (pin "8") (pinfunction "IO0_8") (pintype "bidirectional"))
      (node (ref "U3") (pin "3") (pinfunction "SQW/~{INT}_3") (pintype "output"))
    )
    (net (code "17") (name "IO{slash}BOOT") (class "Default")
      (node (ref "BOOT_BUTTON") (pin "4") (pinfunction "4_4") (pintype "passive"))
      (node (ref "C6") (pin "1") (pinfunction "1_1") (pintype "passive"))
      (node (ref "R_BOOT") (pin "1") (pinfunction "1_1") (pintype "passive"))
      (node (ref "U2") (pin "15") (pinfunction "IO9_15") (pintype "bidirectional"))
    )
    (net (code "18") (name "IO{slash}CHANGE") (class "Default")
      (node (ref "C10") (pin "1") (pinfunction "1_1") (pintype "passive"))
      (node (ref "CHANGE_BUTTON") (pin "4") (pinfunction "4_4") (pintype "passive"))
      (node (ref "R_CHANGE") (pin "1") (pinfunction "1_1") (pintype "passive"))
      (node (ref "U2") (pin "23") (pinfunction "IO15_23") (pintype "bidirectional"))
    )
    (net (code "19") (name "MISO") (class "Default")
      (node (ref "D12") (pin "2") (pinfunction "2_2") (pintype "passive"))
      (node (ref "J4") (pin "P7") (pinfunction "DAT0_P7") (pintype "bidirectional"))
      (node (ref "R8") (pin "1") (pinfunction "1_1") (pintype "passive"))
      (node (ref "TP6") (pin "TP") (pinfunction "TP_TP") (pintype "input"))
      (node (ref "U1") (pin "2") (pinfunction "DO(IO1)_2") (pintype "bidirectional"))
      (node (ref "U2") (pin "27") (pinfunction "IO2_27") (pintype "bidirectional"))
    )
    (net (code "20") (name "MOSI") (class "Default")
      (node (ref "D11") (pin "2") (pinfunction "2_2") (pintype "passive"))
      (node (ref "FH34SRJ-24S-0.5SH_99_1") (pin "14") (pinfunction "14_14") (pintype "bidirectional"))
      (node (ref "J4") (pin "P3") (pinfunction "CMD_P3") (pintype "bidirectional"))
      (node (ref "R7") (pin "1") (pinfunction "1_1") (pintype "passive"))
      (node (ref "TP7") (pin "TP") (pinfunction "TP_TP") (pintype "input"))
      (node (ref "U1") (pin "5") (pinfunction "DI(IO0)_5") (pintype "bidirectional"))
      (node (ref "U2") (pin "7") (pinfunction "IO7_7") (pintype "bidirectional"))
    )
    (net (code "21") (name "Net-(CHG_LED-PadC)") (class "Default")
      (node (ref "CHG_LED") (pin "C") (pinfunction "C_C") (pintype "passive"))
      (node (ref "R1_BAT") (pin "1") (pinfunction "1_1") (pintype "passive"))
    )
    (net (code "22") (name "Net-(D2-CATHODE)") (class "Default")
      (node (ref "C1_BAT1") (pin "1") (pinfunction "1_1") (pintype "passive"))
      (node (ref "D2") (pin "1") (pinfunction "CATHODE_1") (pintype "bidirectional"))
      (node (ref "IC4") (pin "1") (pinfunction "VIN_1") (pintype "bidirectional"))
      (node (ref "IC4") (pin "3") (pinfunction "CE_3") (pintype "bidirectional"))
    )
    (net (code "23") (name "Net-(D3-A)") (class "Default")
      (node (ref "C4") (pin "1") (pinfunction "1_1") (pintype "passive"))
      (node (ref "D3") (pin "2") (pinfunction "A_2") (pintype "bidirectional"))
      (node (ref "D4") (pin "1") (pinfunction "K_1") (pintype "bidirectional"))
    )
    (net (code "24") (name "Net-(D7-CATHODE)") (class "Default")
      (node (ref "D7") (pin "1") (pinfunction "CATHODE_1") (pintype "bidirectional"))
      (node (ref "R_CAPACITOR") (pin "2") (pinfunction "2_2") (pintype "passive"))
    )
    (net (code "25") (name "Net-(EPD_C1-Pad2)") (class "Default")
      (node (ref "EPD_C1") (pin "2") (pinfunction "2_2") (pintype "passive"))
      (node (ref "FH34SRJ-24S-0.5SH_99_1") (pin "4") (pinfunction "4_4") (pintype "bidirectional"))
    )
    (net (code "26") (name "Net-(EPD_C2-Pad2)") (class "Default")
      (node (ref "EPD_C2") (pin "2") (pinfunction "2_2") (pintype "passive"))
      (node (ref "FH34SRJ-24S-0.5SH_99_1") (pin "5") (pinfunction "5_5") (pintype "bidirectional"))
    )
    (net (code "27") (name "Net-(EPD_C6-Pad2)") (class "Default")
      (node (ref "EPD_C6") (pin "2") (pinfunction "2_2") (pintype "passive"))
      (node (ref "FH34SRJ-24S-0.5SH_99_1") (pin "18") (pinfunction "18_18") (pintype "bidirectional"))
    )
    (net (code "28") (name "Net-(EPD_C7-Pad2)") (class "Default")
      (node (ref "EPD_C7") (pin "2") (pinfunction "2_2") (pintype "passive"))
      (node (ref "FH34SRJ-24S-0.5SH_99_1") (pin "19") (pinfunction "19_19") (pintype "bidirectional"))
    )
    (net (code "29") (name "Net-(EPD_C8-Pad2)") (class "Default")
      (node (ref "EPD_C8") (pin "2") (pinfunction "2_2") (pintype "passive"))
      (node (ref "FH34SRJ-24S-0.5SH_99_1") (pin "20") (pinfunction "20_20") (pintype "bidirectional"))
    )
    (net (code "30") (name "Net-(EPD_C10-Pad2)") (class "Default")
      (node (ref "EPD_C10") (pin "2") (pinfunction "2_2") (pintype "passive"))
      (node (ref "FH34SRJ-24S-0.5SH_99_1") (pin "22") (pinfunction "22_22") (pintype "bidirectional"))
    )
    (net (code "31") (name "Net-(EPD_C12-Pad2)") (class "Default")
      (node (ref "EPD_C12") (pin "2") (pinfunction "2_2") (pintype "passive"))
      (node (ref "FH34SRJ-24S-0.5SH_99_1") (pin "24") (pinfunction "24_24") (pintype "bidirectional"))
    )
    (net (code "32") (name "Net-(IC2-CT)") (class "Default")
      (node (ref "C_DELAY") (pin "2") (pinfunction "2_2") (pintype "passive"))
      (node (ref "IC2") (pin "5") (pinfunction "CT_5") (pintype "bidirectional"))
    )
    (net (code "33") (name "Net-(J2-PadA5)") (class "Default")
      (node (ref "J2") (pin "A5") (pinfunction "A5_A5") (pintype "bidirectional"))
      (node (ref "R2_USB1") (pin "2") (pinfunction "2_2") (pintype "passive"))
    )
    (net (code "34") (name "Net-(J2-PadB5)") (class "Default")
      (node (ref "J2") (pin "B5") (pinfunction "B5_B5") (pintype "bidirectional"))
      (node (ref "R2_USB") (pin "1") (pinfunction "1_1") (pintype "passive"))
    )
    (net (code "35") (name "Net-(MCP1-PROG)") (class "Default")
      (node (ref "MCP1") (pin "5") (pinfunction "PROG_5") (pintype "input"))
      (node (ref "R2_BAT") (pin "2") (pinfunction "2_2") (pintype "passive"))
    )
    (net (code "36") (name "Net-(MCP1-STAT)") (class "Default")
      (node (ref "MCP1") (pin "1") (pinfunction "STAT_1") (pintype "output"))
      (node (ref "R1_BAT") (pin "2") (pinfunction "2_2") (pintype "passive"))
    )
    (net (code "37") (name "PREVGH") (class "Default")
      (node (ref "D5") (pin "1") (pinfunction "K_1") (pintype "bidirectional"))
      (node (ref "EPD_C9") (pin "2") (pinfunction "2_2") (pintype "passive"))
      (node (ref "FH34SRJ-24S-0.5SH_99_1") (pin "21") (pinfunction "21_21") (pintype "bidirectional"))
    )
    (net (code "38") (name "PREVGL") (class "Default")
      (node (ref "D4") (pin "2") (pinfunction "A_2") (pintype "bidirectional"))
      (node (ref "EPD_C11") (pin "2") (pinfunction "2_2") (pintype "passive"))
      (node (ref "FH34SRJ-24S-0.5SH_99_1") (pin "23") (pinfunction "23_23") (pintype "bidirectional"))
    )
    (net (code "39") (name "RESE") (class "Default")
      (node (ref "FH34SRJ-24S-0.5SH_99_1") (pin "3") (pinfunction "3_3") (pintype "bidirectional"))
      (node (ref "Q3") (pin "2") (pinfunction "S_2") (pintype "bidirectional"))
      (node (ref "R3") (pin "2") (pinfunction "2_2") (pintype "passive"))
    )
    (net (code "40") (name "RESE'") (class "Default")
      (node (ref "R2") (pin "2") (pinfunction "2_2") (pintype "passive"))
      (node (ref "R3") (pin "1") (pinfunction "1_1") (pintype "passive"))
      (node (ref "SJ1") (pin "2") (pinfunction "2_2") (pintype "passive"))
    )
    (net (code "41") (name "RESET") (class "Default")
      (node (ref "C5") (pin "1") (pinfunction "1_1") (pintype "passive"))
      (node (ref "IC2") (pin "1") (pinfunction "VOUT_1") (pintype "bidirectional"))
      (node (ref "RESET_BUTTON") (pin "3") (pinfunction "3_3") (pintype "passive"))
      (node (ref "RESET_BUTTON") (pin "4") (pinfunction "4_4") (pintype "passive"))
      (node (ref "R_RESET") (pin "1") (pinfunction "1_1") (pintype "passive"))
      (node (ref "U2") (pin "3") (pinfunction "EN_3") (pintype "input"))
    )
    (net (code "42") (name "RTC_RST") (class "Default")
      (node (ref "U2") (pin "16") (pinfunction "IO18_16") (pintype "bidirectional"))
      (node (ref "U3") (pin "4") (pinfunction "~{RST}_4") (pintype "input"))
    )
    (net (code "43") (name "RX") (class "Default")
      (node (ref "TP2") (pin "TP") (pinfunction "TP_TP") (pintype "input"))
      (node (ref "U2") (pin "24") (pinfunction "RXD0/GPIO17_24") (pintype "bidirectional"))
    )
    (net (code "44") (name "SCK") (class "Default")
      (node (ref "D10") (pin "2") (pinfunction "2_2") (pintype "passive"))
      (node (ref "FH34SRJ-24S-0.5SH_99_1") (pin "13") (pinfunction "13_13") (pintype "bidirectional"))
      (node (ref "J4") (pin "P5") (pinfunction "CLK_P5") (pintype "bidirectional"))
      (node (ref "R6") (pin "1") (pinfunction "1_1") (pintype "passive"))
      (node (ref "TP8") (pin "TP") (pinfunction "TP_TP") (pintype "input"))
      (node (ref "U1") (pin "6") (pinfunction "CLK_6") (pintype "input"))
      (node (ref "U2") (pin "6") (pinfunction "IO6_6") (pintype "bidirectional"))
    )
    (net (code "45") (name "SCL") (class "Default")
      (node (ref "J1") (pin "4") (pinfunction "4_4") (pintype "passive"))
      (node (ref "R2_PINH") (pin "1") (pinfunction "1_1") (pintype "passive"))
      (node (ref "SENSOR2") (pin "4") (pinfunction "SCK_4") (pintype "input"))
      (node (ref "U2") (pin "20") (pinfunction "IO22_20") (pintype "bidirectional"))
      (node (ref "U3") (pin "16") (pinfunction "SCL_16") (pintype "input"))
      (node (ref "U4") (pin "7") (pinfunction "SCL_7") (pintype "input"))
    )
    (net (code "46") (name "SDA") (class "Default")
      (node (ref "J1") (pin "3") (pinfunction "3_3") (pintype "passive"))
      (node (ref "R1_PINH") (pin "1") (pinfunction "1_1") (pintype "passive"))
      (node (ref "SENSOR2") (pin "3") (pinfunction "SDI_3") (pintype "bidirectional"))
      (node (ref "U2") (pin "19") (pinfunction "IO21_19") (pintype "bidirectional"))
      (node (ref "U3") (pin "15") (pinfunction "SDA_15") (pintype "bidirectional"))
      (node (ref "U4") (pin "8") (pinfunction "SDA_8") (pintype "bidirectional"))
    )
    (net (code "47") (name "SRC") (class "Default")
      (node (ref "C4") (pin "2") (pinfunction "2_2") (pintype "passive"))
      (node (ref "D5") (pin "2") (pinfunction "A_2") (pintype "bidirectional"))
      (node (ref "L1") (pin "1") (pinfunction "1_1") (pintype "passive"))
      (node (ref "Q3") (pin "3") (pinfunction "D_3") (pintype "bidirectional"))
    )
    (net (code "48") (name "SS_SD") (class "Default")
      (node (ref "D8") (pin "2") (pinfunction "2_2") (pintype "passive"))
      (node (ref "J4") (pin "P2") (pinfunction "CD/DAT3_P2") (pintype "bidirectional"))
      (node (ref "R10") (pin "1") (pinfunction "1_1") (pintype "passive"))
      (node (ref "U2") (pin "4") (pinfunction "IO4_4") (pintype "bidirectional"))
    )
    (net (code "49") (name "TX") (class "Default")
      (node (ref "TP1") (pin "TP") (pinfunction "TP_TP") (pintype "input"))
      (node (ref "U2") (pin "25") (pinfunction "TXD0/GPIO16_25") (pintype "bidirectional"))
    )
    (net (code "50") (name "USB_D+") (class "Default")
      (node (ref "D1") (pin "1") (pinfunction "I/O1_1_1") (pintype "bidirectional"))
      (node (ref "U2") (pin "14") (pinfunction "IO13_14") (pintype "bidirectional"))
    )
    (net (code "51") (name "USB_D-") (class "Default")
      (node (ref "D1") (pin "3") (pinfunction "I/O2_1_3") (pintype "bidirectional"))
      (node (ref "U2") (pin "13") (pinfunction "IO12_13") (pintype "bidirectional"))
    )
    (net (code "52") (name "VBAT") (class "Default")
      (node (ref "C2_BAT") (pin "1") (pinfunction "1_1") (pintype "passive"))
      (node (ref "MCP1") (pin "3") (pinfunction "VBAT_3") (pintype "power_in"))
      (node (ref "Q1") (pin "3") (pinfunction "D_3") (pintype "bidirectional"))
      (node (ref "TP3") (pin "TP") (pinfunction "TP_TP") (pintype "input"))
      (node (ref "U4") (pin "2") (pinfunction "CELL_2") (pintype "power_in"))
      (node (ref "U4") (pin "3") (pinfunction "VDD_3") (pintype "power_in"))
    )
    (net (code "53") (name "VBUS") (class "Default")
      (node (ref "C1_BAT") (pin "1") (pinfunction "1_1") (pintype "passive"))
      (node (ref "C4_USB") (pin "1") (pinfunction "1_1") (pintype "passive"))
      (node (ref "C5_USB") (pin "1") (pinfunction "1_1") (pintype "passive"))
      (node (ref "CHG_LED") (pin "A") (pinfunction "A_A") (pintype "passive"))
      (node (ref "D1") (pin "5") (pinfunction "VBUS_5") (pintype "bidirectional"))
      (node (ref "D2") (pin "2") (pinfunction "ANODE_2") (pintype "bidirectional"))
      (node (ref "MCP1") (pin "4") (pinfunction "VIN_4") (pintype "power_in"))
      (node (ref "PFMF.050.1") (pin "2") (pinfunction "2_2") (pintype "passive"))
      (node (ref "Q1") (pin "1") (pinfunction "G_1") (pintype "bidirectional"))
      (node (ref "R1_PWRUSB") (pin "2") (pinfunction "2_2") (pintype "passive"))
      (node (ref "TP14") (pin "TP") (pinfunction "TP_TP") (pintype "input"))
    )
    (net (code "54") (name "VRTC") (class "Default")
      (node (ref "C10_SUPERCAP") (pin "2") (pinfunction "2_2") (pintype "passive"))
      (node (ref "C8") (pin "1") (pinfunction "1_1") (pintype "passive"))
      (node (ref "R_CAPACITOR") (pin "1") (pinfunction "1_1") (pintype "passive"))
      (node (ref "U3") (pin "14") (pinfunction "VBAT_14") (pintype "power_in"))
    )
    (net (code "55") (name "VUSB") (class "Default")
      (node (ref "J2") (pin "A4") (pinfunction "A4_A4") (pintype "bidirectional"))
      (node (ref "J2") (pin "B4") (pinfunction "B4_B4") (pintype "bidirectional"))
      (node (ref "J2") (pin "B9") (pinfunction "B9_B9") (pintype "bidirectional"))
      (node (ref "PFMF.050.1") (pin "1") (pinfunction "1_1") (pintype "passive"))
    )
    (net (code "56") (name "unconnected-(BOOT_BUTTON-Pad1)") (class "Default")
      (node (ref "BOOT_BUTTON") (pin "1") (pinfunction "1_1") (pintype "passive"))
    )
    (net (code "57") (name "unconnected-(BOOT_BUTTON-Pad3)") (class "Default")
      (node (ref "BOOT_BUTTON") (pin "3") (pinfunction "3_3") (pintype "passive"))
    )
    (net (code "58") (name "unconnected-(CHANGE_BUTTON-Pad1)") (class "Default")
      (node (ref "CHANGE_BUTTON") (pin "1") (pinfunction "1_1") (pintype "passive"))
    )
    (net (code "59") (name "unconnected-(CHANGE_BUTTON-Pad3)") (class "Default")
      (node (ref "CHANGE_BUTTON") (pin "3") (pinfunction "3_3") (pintype "passive"))
    )
    (net (code "60") (name "unconnected-(FH34SRJ-24S-0.5SH_99_1-Pad1)") (class "Default")
      (node (ref "FH34SRJ-24S-0.5SH_99_1") (pin "1") (pinfunction "1_1") (pintype "bidirectional"))
    )
    (net (code "61") (name "unconnected-(FH34SRJ-24S-0.5SH_99_1-Pad6)") (class "Default")
      (node (ref "FH34SRJ-24S-0.5SH_99_1") (pin "6") (pinfunction "6_6") (pintype "bidirectional"))
    )
    (net (code "62") (name "unconnected-(FH34SRJ-24S-0.5SH_99_1-Pad7)") (class "Default")
      (node (ref "FH34SRJ-24S-0.5SH_99_1") (pin "7") (pinfunction "7_7") (pintype "bidirectional"))
    )
    (net (code "63") (name "unconnected-(IC2-NC-Pad4)") (class "Default")
      (node (ref "IC2") (pin "4") (pinfunction "NC_4") (pintype "no_connect"))
    )
    (net (code "64") (name "unconnected-(IC4-NC-Pad4)") (class "Default")
      (node (ref "IC4") (pin "4") (pinfunction "NC_4") (pintype "no_connect"))
    )
    (net (code "65") (name "unconnected-(J2-PadA8)") (class "Default")
      (node (ref "J2") (pin "A8") (pinfunction "A8_A8") (pintype "bidirectional"))
    )
    (net (code "66") (name "unconnected-(J2-PadA9)") (class "Default")
      (node (ref "J2") (pin "A9") (pinfunction "A9_A9") (pintype "bidirectional"))
    )
    (net (code "67") (name "unconnected-(J2-PadB8)") (class "Default")
      (node (ref "J2") (pin "B8") (pinfunction "B8_B8") (pintype "bidirectional"))
    )
    (net (code "68") (name "unconnected-(J4-DAT1-PadP8)") (class "Default")
      (node (ref "J4") (pin "P8") (pinfunction "DAT1_P8") (pintype "bidirectional"))
    )
    (net (code "69") (name "unconnected-(J4-DAT2-PadP1)") (class "Default")
      (node (ref "J4") (pin "P1") (pinfunction "DAT2_P1") (pintype "bidirectional"))
    )
    (net (code "70") (name "unconnected-(J4-DETECTION_1-PadS1)") (class "Default")
      (node (ref "J4") (pin "S1") (pinfunction "DETECTION_1_S1") (pintype "bidirectional"))
    )
    (net (code "71") (name "unconnected-(J4-DETECTION_2-PadS2)") (class "Default")
      (node (ref "J4") (pin "S2") (pinfunction "DETECTION_2_S2") (pintype "bidirectional"))
    )
    (net (code "72") (name "unconnected-(Q1-S-Pad2)") (class "Default")
      (node (ref "Q1") (pin "2") (pinfunction "S_2") (pintype "bidirectional"))
    )
    (net (code "73") (name "unconnected-(U2-NC-Pad22)") (class "Default")
      (node (ref "U2") (pin "22") (pinfunction "NC_22") (pintype "no_connect"))
    )
    (net (code "74") (name "unconnected-(U4-~{ALERT}-Pad5)") (class "Default")
      (node (ref "U4") (pin "5") (pinfunction "~{ALERT}_5") (pintype "output"))
    )
  )
)
